# robert_sullivan_zoetrope_sch.net
KiCad netlist of a schematic drawn in EAGLE
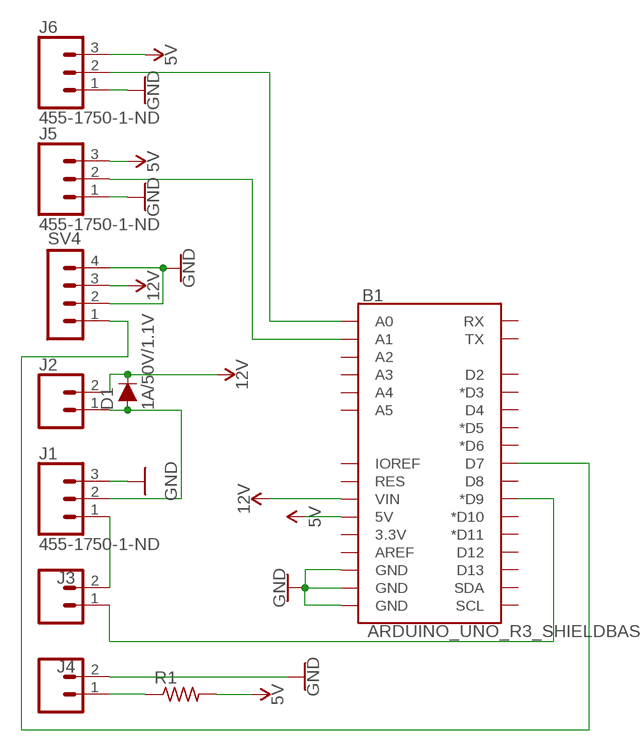
[diagram p0: schematic, sheet 1]

(export (version "E")
  (design (tool "Eeschema 10.0.6"))
  (components
    (comp (ref "B1")
      (value "ARDUINO_UNO_R3_SHIELDBASIC")
      (footprint "eagle-import:UNO_R3_SHIELD")
      (libsource (lib "eagle-import") (part "ARDUINO_UNO_R3_SHIELDBASIC"))
    )
    (comp (ref "D1")
      (value "1A/50V/1.1V")
      (footprint "eagle-import:DIODE-1N4001")
      (libsource (lib "eagle-import") (part "DIODE-PTH"))
    )
    (comp (ref "J1")
      (value "455-1750-1-ND")
      (footprint "eagle-import:1X03")
      (libsource (lib "eagle-import") (part "CONN_03"))
    )
    (comp (ref "J2")
      (value "CONN_02")
      (footprint "eagle-import:1X02")
      (libsource (lib "eagle-import") (part "CONN_02"))
    )
    (comp (ref "J3")
      (value "CONN_02")
      (footprint "eagle-import:1X02")
      (libsource (lib "eagle-import") (part "CONN_02"))
    )
    (comp (ref "J4")
      (value "CONN_02")
      (footprint "eagle-import:1X02")
      (libsource (lib "eagle-import") (part "CONN_02"))
    )
    (comp (ref "J5")
      (value "455-1750-1-ND")
      (footprint "eagle-import:1X03")
      (libsource (lib "eagle-import") (part "CONN_03"))
    )
    (comp (ref "J6")
      (value "455-1750-1-ND")
      (footprint "eagle-import:1X03")
      (libsource (lib "eagle-import") (part "CONN_03"))
    )
    (comp (ref "R1")
      (value "R-US_0309/12")
      (footprint "eagle-import:0309_12")
      (libsource (lib "eagle-import") (part "R-US_0309/12"))
    )
    (comp (ref "SV4")
      (value "MA04-1")
      (footprint "eagle-import:MA04-1")
      (libsource (lib "eagle-import") (part "MA04-1"))
    )
  )
  (nets
    (net (code "1") (name "5V") (class "Default")
      (node (ref "B1") (pin "5V") (pinfunction "5V_5V") (pintype "bidirectional"))
      (node (ref "J5") (pin "3") (pinfunction "3_3") (pintype "passive"))
      (node (ref "J6") (pin "3") (pinfunction "3_3") (pintype "passive"))
      (node (ref "R1") (pin "2") (pinfunction "2_2") (pintype "passive"))
    )
    (net (code "2") (name "12V") (class "Default")
      (node (ref "B1") (pin "VIN") (pinfunction "VIN_VIN") (pintype "bidirectional"))
      (node (ref "D1") (pin "C") (pinfunction "C_C") (pintype "passive"))
      (node (ref "J2") (pin "2") (pinfunction "2_2") (pintype "passive"))
      (node (ref "SV4") (pin "3") (pinfunction "3_3") (pintype "passive"))
    )
    (net (code "3") (name "GND") (class "Default")
      (node (ref "B1") (pin "GND@0") (pinfunction "GND_GND@0") (pintype "bidirectional"))
      (node (ref "B1") (pin "GND@1") (pinfunction "GND_GND@1") (pintype "bidirectional"))
      (node (ref "B1") (pin "GND@2") (pinfunction "GND_GND@2") (pintype "bidirectional"))
      (node (ref "J1") (pin "3") (pinfunction "3_3") (pintype "passive"))
      (node (ref "J4") (pin "2") (pinfunction "2_2") (pintype "passive"))
      (node (ref "J5") (pin "1") (pinfunction "1_1") (pintype "passive"))
      (node (ref "J6") (pin "1") (pinfunction "1_1") (pintype "passive"))
      (node (ref "SV4") (pin "2") (pinfunction "2_2") (pintype "passive"))
      (node (ref "SV4") (pin "4") (pinfunction "4_4") (pintype "passive"))
    )
    (net (code "4") (name "Net-(B1-*D9)") (class "Default")
      (node (ref "B1") (pin "D9") (pinfunction "*D9_D9") (pintype "bidirectional"))
      (node (ref "J3") (pin "1") (pinfunction "1_1") (pintype "passive"))
    )
    (net (code "5") (name "Net-(B1-PadA0)") (class "Default")
      (node (ref "B1") (pin "A0") (pinfunction "A0_A0") (pintype "bidirectional"))
      (node (ref "J6") (pin "2") (pinfunction "2_2") (pintype "passive"))
    )
    (net (code "6") (name "Net-(B1-PadA1)") (class "Default")
      (node (ref "B1") (pin "A1") (pinfunction "A1_A1") (pintype "bidirectional"))
      (node (ref "J5") (pin "2") (pinfunction "2_2") (pintype "passive"))
    )
    (net (code "7") (name "Net-(B1-PadD7)") (class "Default")
      (node (ref "B1") (pin "D7") (pinfunction "D7_D7") (pintype "bidirectional"))
      (node (ref "SV4") (pin "1") (pinfunction "1_1") (pintype "passive"))
    )
    (net (code "8") (name "Net-(D1-PadA)") (class "Default")
      (node (ref "D1") (pin "A") (pinfunction "A_A") (pintype "passive"))
      (node (ref "J1") (pin "2") (pinfunction "2_2") (pintype "passive"))
      (node (ref "J2") (pin "1") (pinfunction "1_1") (pintype "passive"))
    )
    (net (code "9") (name "Net-(J1-Pad1)") (class "Default")
      (node (ref "J1") (pin "1") (pinfunction "1_1") (pintype "passive"))
      (node (ref "J3") (pin "2") (pinfunction "2_2") (pintype "passive"))
    )
    (net (code "10") (name "Net-(J4-Pad1)") (class "Default")
      (node (ref "J4") (pin "1") (pinfunction "1_1") (pintype "passive"))
      (node (ref "R1") (pin "1") (pinfunction "1_1") (pintype "passive"))
    )
    (net (code "11") (name "unconnected-(B1-*D3-PadD3)") (class "Default")
      (node (ref "B1") (pin "D3") (pinfunction "*D3_D3") (pintype "bidirectional"))
    )
    (net (code "12") (name "unconnected-(B1-*D5-PadD5)") (class "Default")
      (node (ref "B1") (pin "D5") (pinfunction "*D5_D5") (pintype "bidirectional"))
    )
    (net (code "13") (name "unconnected-(B1-*D6-PadD6)") (class "Default")
      (node (ref "B1") (pin "D6") (pinfunction "*D6_D6") (pintype "bidirectional"))
    )
    (net (code "14") (name "unconnected-(B1-*D10-PadD10)") (class "Default")
      (node (ref "B1") (pin "D10") (pinfunction "*D10_D10") (pintype "bidirectional"))
    )
    (net (code "15") (name "unconnected-(B1-*D11-PadD11)") (class "Default")
      (node (ref "B1") (pin "D11") (pinfunction "*D11_D11") (pintype "bidirectional"))
    )
    (net (code "16") (name "unconnected-(B1-Pad3.3V)") (class "Default")
      (node (ref "B1") (pin "3.3V") (pinfunction "3.3V_3.3V") (pintype "bidirectional"))
    )
    (net (code "17") (name "unconnected-(B1-PadA2)") (class "Default")
      (node (ref "B1") (pin "A2") (pinfunction "A2_A2") (pintype "bidirectional"))
    )
    (net (code "18") (name "unconnected-(B1-PadA3)") (class "Default")
      (node (ref "B1") (pin "A3") (pinfunction "A3_A3") (pintype "bidirectional"))
    )
    (net (code "19") (name "unconnected-(B1-PadA4)") (class "Default")
      (node (ref "B1") (pin "A4") (pinfunction "A4_A4") (pintype "bidirectional"))
    )
    (net (code "20") (name "unconnected-(B1-PadA5)") (class "Default")
      (node (ref "B1") (pin "A5") (pinfunction "A5_A5") (pintype "bidirectional"))
    )
    (net (code "21") (name "unconnected-(B1-PadAREF)") (class "Default")
      (node (ref "B1") (pin "AREF") (pinfunction "AREF_AREF") (pintype "bidirectional"))
    )
    (net (code "22") (name "unconnected-(B1-PadD2)") (class "Default")
      (node (ref "B1") (pin "D2") (pinfunction "D2_D2") (pintype "bidirectional"))
    )
    (net (code "23") (name "unconnected-(B1-PadD4)") (class "Default")
      (node (ref "B1") (pin "D4") (pinfunction "D4_D4") (pintype "bidirectional"))
    )
    (net (code "24") (name "unconnected-(B1-PadD8)") (class "Default")
      (node (ref "B1") (pin "D8") (pinfunction "D8_D8") (pintype "bidirectional"))
    )
    (net (code "25") (name "unconnected-(B1-PadD12)") (class "Default")
      (node (ref "B1") (pin "D12") (pinfunction "D12_D12") (pintype "bidirectional"))
    )
    (net (code "26") (name "unconnected-(B1-PadD13)") (class "Default")
      (node (ref "B1") (pin "D13") (pinfunction "D13_D13") (pintype "bidirectional"))
    )
    (net (code "27") (name "unconnected-(B1-PadIOREF)") (class "Default")
      (node (ref "B1") (pin "IOREF") (pinfunction "IOREF_IOREF") (pintype "bidirectional"))
    )
    (net (code "28") (name "unconnected-(B1-PadRES)") (class "Default")
      (node (ref "B1") (pin "RES") (pinfunction "RES_RES") (pintype "bidirectional"))
    )
    (net (code "29") (name "unconnected-(B1-PadRX)") (class "Default")
      (node (ref "B1") (pin "RX") (pinfunction "RX_RX") (pintype "bidirectional"))
    )
    (net (code "30") (name "unconnected-(B1-PadSCL)") (class "Default")
      (node (ref "B1") (pin "SCL") (pinfunction "SCL_SCL") (pintype "bidirectional"))
    )
    (net (code "31") (name "unconnected-(B1-PadSDA)") (class "Default")
      (node (ref "B1") (pin "SDA") (pinfunction "SDA_SDA") (pintype "bidirectional"))
    )
    (net (code "32") (name "unconnected-(B1-PadTX)") (class "Default")
      (node (ref "B1") (pin "TX") (pinfunction "TX_TX") (pintype "bidirectional"))
    )
  )
)
